# P2_AudioInput.net
KiCad netlist of a schematic drawn in Altium Designer
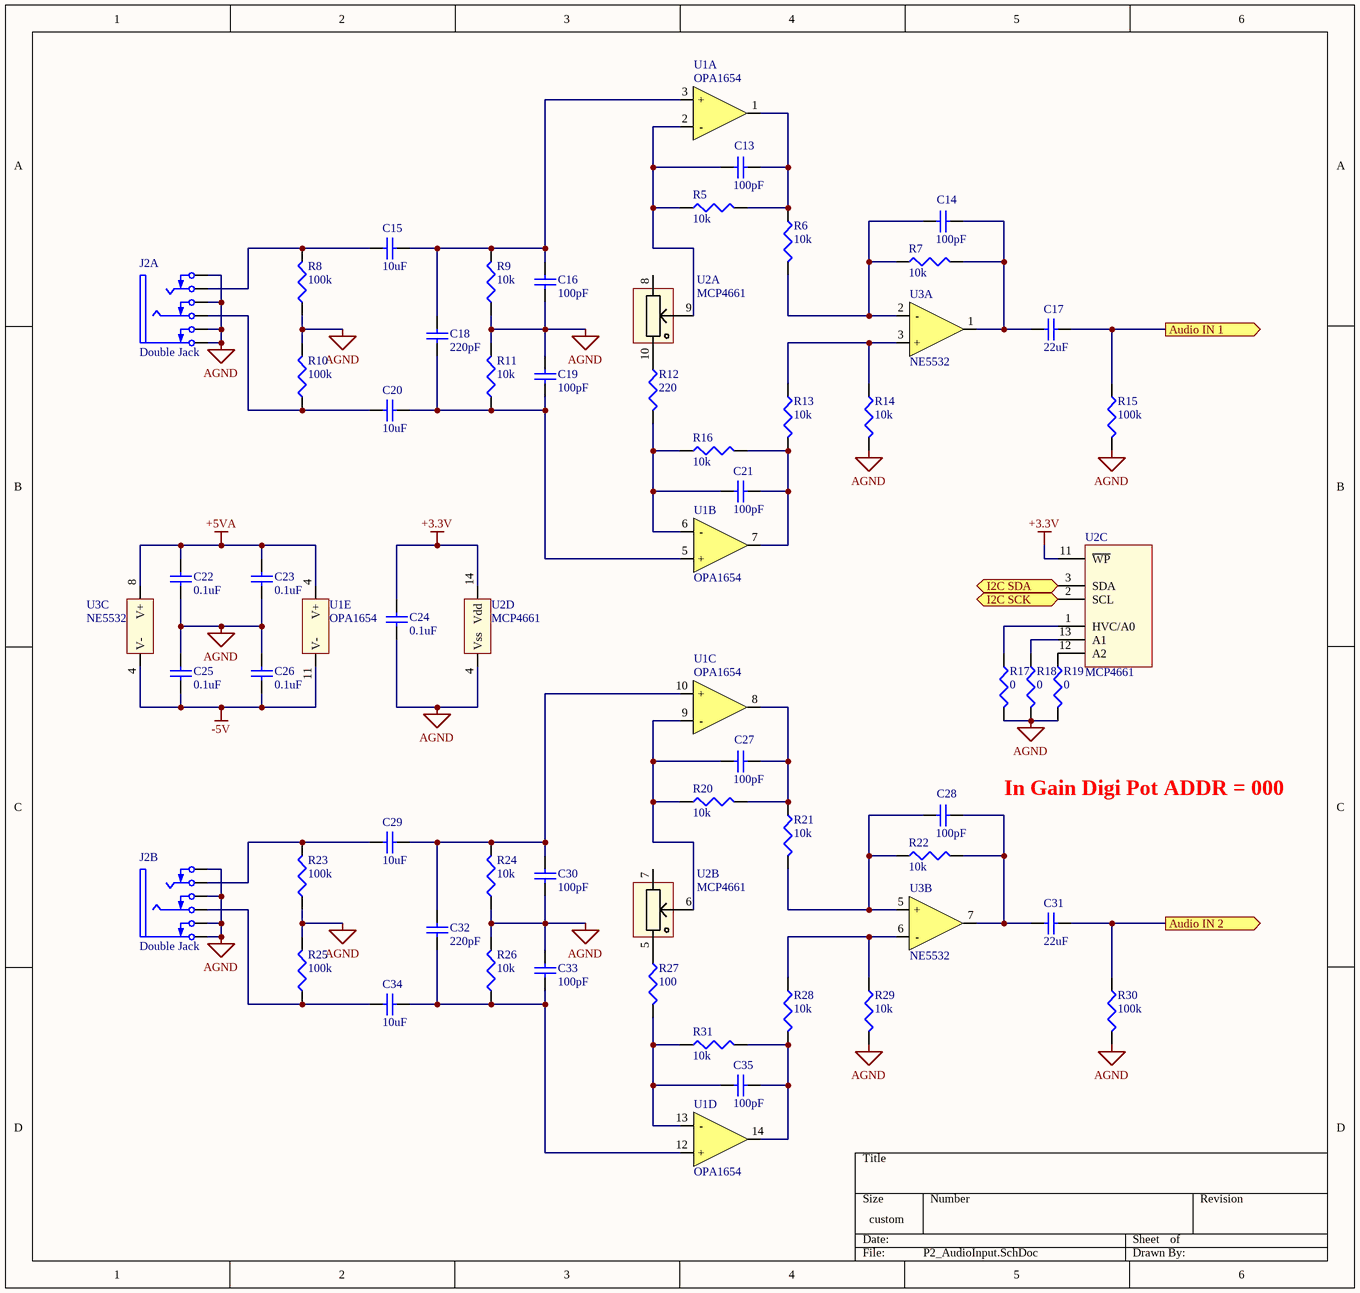
[diagram p0: P2_AudioInput.SchDoc]

(export (version "E")
  (design (tool "Eeschema 10.0.6"))
  (components
    (comp (ref "C13")
      (value "100pF")
      (footprint "CAP 0603 (1608 metric)")
      (description "Capacitor (Semiconductor SIM Model)")
      (libsource (lib "Miscellaneous Devices") (part "Cap Semi"))
    )
    (comp (ref "C14")
      (value "100pF")
      (footprint "CAP 0603 (1608 metric)")
      (description "Capacitor (Semiconductor SIM Model)")
      (libsource (lib "Miscellaneous Devices") (part "Cap Semi"))
    )
    (comp (ref "C15")
      (value "10uF")
      (footprint "CAP 0603 (1608 metric)")
      (description "Capacitor (Semiconductor SIM Model)")
      (libsource (lib "Miscellaneous Devices") (part "Cap Semi"))
    )
    (comp (ref "C16")
      (value "100pF")
      (footprint "CAP 0603 (1608 metric)")
      (description "Capacitor (Semiconductor SIM Model)")
      (libsource (lib "Miscellaneous Devices") (part "Cap Semi"))
    )
    (comp (ref "C17")
      (value "22uF")
      (footprint "CAP 0603 (1608 metric)")
      (description "Capacitor (Semiconductor SIM Model)")
      (libsource (lib "Miscellaneous Devices") (part "Cap Semi"))
    )
    (comp (ref "C18")
      (value "220pF")
      (footprint "CAP 0603 (1608 metric)")
      (description "Capacitor (Semiconductor SIM Model)")
      (libsource (lib "Miscellaneous Devices") (part "Cap Semi"))
    )
    (comp (ref "C19")
      (value "100pF")
      (footprint "CAP 0603 (1608 metric)")
      (description "Capacitor (Semiconductor SIM Model)")
      (libsource (lib "Miscellaneous Devices") (part "Cap Semi"))
    )
    (comp (ref "C20")
      (value "10uF")
      (footprint "CAP 0603 (1608 metric)")
      (description "Capacitor (Semiconductor SIM Model)")
      (libsource (lib "Miscellaneous Devices") (part "Cap Semi"))
    )
    (comp (ref "C21")
      (value "100pF")
      (footprint "CAP 0603 (1608 metric)")
      (description "Capacitor (Semiconductor SIM Model)")
      (libsource (lib "Miscellaneous Devices") (part "Cap Semi"))
    )
    (comp (ref "C22")
      (value "0.1uF")
      (footprint "CAP 0603 (1608 metric)")
      (description "Capacitor (Semiconductor SIM Model)")
      (libsource (lib "Miscellaneous Devices") (part "Cap Semi"))
    )
    (comp (ref "C23")
      (value "0.1uF")
      (footprint "CAP 0603 (1608 metric)")
      (description "Capacitor (Semiconductor SIM Model)")
      (libsource (lib "Miscellaneous Devices") (part "Cap Semi"))
    )
    (comp (ref "C24")
      (value "0.1uF")
      (footprint "CAP 0603 (1608 metric)")
      (description "Capacitor (Semiconductor SIM Model)")
      (libsource (lib "Miscellaneous Devices") (part "Cap Semi"))
    )
    (comp (ref "C25")
      (value "0.1uF")
      (footprint "CAP 0603 (1608 metric)")
      (description "Capacitor (Semiconductor SIM Model)")
      (libsource (lib "Miscellaneous Devices") (part "Cap Semi"))
    )
    (comp (ref "C26")
      (value "0.1uF")
      (footprint "CAP 0603 (1608 metric)")
      (description "Capacitor (Semiconductor SIM Model)")
      (libsource (lib "Miscellaneous Devices") (part "Cap Semi"))
    )
    (comp (ref "C27")
      (value "100pF")
      (footprint "CAP 0603 (1608 metric)")
      (description "Capacitor (Semiconductor SIM Model)")
      (libsource (lib "Miscellaneous Devices") (part "Cap Semi"))
    )
    (comp (ref "C28")
      (value "100pF")
      (footprint "CAP 0603 (1608 metric)")
      (description "Capacitor (Semiconductor SIM Model)")
      (libsource (lib "Miscellaneous Devices") (part "Cap Semi"))
    )
    (comp (ref "C29")
      (value "10uF")
      (footprint "CAP 0603 (1608 metric)")
      (description "Capacitor (Semiconductor SIM Model)")
      (libsource (lib "Miscellaneous Devices") (part "Cap Semi"))
    )
    (comp (ref "C30")
      (value "100pF")
      (footprint "CAP 0603 (1608 metric)")
      (description "Capacitor (Semiconductor SIM Model)")
      (libsource (lib "Miscellaneous Devices") (part "Cap Semi"))
    )
    (comp (ref "C31")
      (value "22uF")
      (footprint "CAP 0603 (1608 metric)")
      (description "Capacitor (Semiconductor SIM Model)")
      (libsource (lib "Miscellaneous Devices") (part "Cap Semi"))
    )
    (comp (ref "C32")
      (value "220pF")
      (footprint "CAP 0603 (1608 metric)")
      (description "Capacitor (Semiconductor SIM Model)")
      (libsource (lib "Miscellaneous Devices") (part "Cap Semi"))
    )
    (comp (ref "C33")
      (value "100pF")
      (footprint "CAP 0603 (1608 metric)")
      (description "Capacitor (Semiconductor SIM Model)")
      (libsource (lib "Miscellaneous Devices") (part "Cap Semi"))
    )
    (comp (ref "C34")
      (value "10uF")
      (footprint "CAP 0603 (1608 metric)")
      (description "Capacitor (Semiconductor SIM Model)")
      (libsource (lib "Miscellaneous Devices") (part "Cap Semi"))
    )
    (comp (ref "C35")
      (value "100pF")
      (footprint "CAP 0603 (1608 metric)")
      (description "Capacitor (Semiconductor SIM Model)")
      (libsource (lib "Miscellaneous Devices") (part "Cap Semi"))
    )
    (comp (ref "J2")
      (value "Double Jack")
      (description "Dual Jack stereo bypassed")
      (libsource (lib "FilterPoC") (part "Dual TRS Jack Bypassed"))
    )
    (comp (ref "R5")
      (value "10k")
      (footprint "RES 0603 (1608 metric)")
      (description "Resistor")
      (libsource (lib "Miscellaneous Devices") (part "Res3"))
    )
    (comp (ref "R6")
      (value "10k")
      (footprint "RES 0603 (1608 metric)")
      (description "Resistor")
      (libsource (lib "Miscellaneous Devices") (part "Res3"))
    )
    (comp (ref "R7")
      (value "10k")
      (footprint "RES 0603 (1608 metric)")
      (description "Resistor")
      (libsource (lib "Miscellaneous Devices") (part "Res3"))
    )
    (comp (ref "R8")
      (value "100k")
      (footprint "RES 0603 (1608 metric)")
      (description "Resistor")
      (libsource (lib "Miscellaneous Devices") (part "Res3"))
    )
    (comp (ref "R9")
      (value "10k")
      (footprint "RES 0603 (1608 metric)")
      (description "Resistor")
      (libsource (lib "Miscellaneous Devices") (part "Res3"))
    )
    (comp (ref "R10")
      (value "100k")
      (footprint "RES 0603 (1608 metric)")
      (description "Resistor")
      (libsource (lib "Miscellaneous Devices") (part "Res3"))
    )
    (comp (ref "R11")
      (value "10k")
      (footprint "RES 0603 (1608 metric)")
      (description "Resistor")
      (libsource (lib "Miscellaneous Devices") (part "Res3"))
    )
    (comp (ref "R12")
      (value "220")
      (footprint "RES 0603 (1608 metric)")
      (description "Resistor")
      (libsource (lib "Miscellaneous Devices") (part "Res3"))
    )
    (comp (ref "R13")
      (value "10k")
      (footprint "RES 0603 (1608 metric)")
      (description "Resistor")
      (libsource (lib "Miscellaneous Devices") (part "Res3"))
    )
    (comp (ref "R14")
      (value "10k")
      (footprint "RES 0603 (1608 metric)")
      (description "Resistor")
      (libsource (lib "Miscellaneous Devices") (part "Res3"))
    )
    (comp (ref "R15")
      (value "100k")
      (footprint "RES 0603 (1608 metric)")
      (description "Resistor")
      (libsource (lib "Miscellaneous Devices") (part "Res3"))
    )
    (comp (ref "R16")
      (value "10k")
      (footprint "RES 0603 (1608 metric)")
      (description "Resistor")
      (libsource (lib "Miscellaneous Devices") (part "Res3"))
    )
    (comp (ref "R17")
      (value "0")
      (footprint "RES 0603 (1608 metric)")
      (description "Resistor")
      (libsource (lib "Miscellaneous Devices") (part "Res3"))
    )
    (comp (ref "R18")
      (value "0")
      (footprint "RES 0603 (1608 metric)")
      (description "Resistor")
      (libsource (lib "Miscellaneous Devices") (part "Res3"))
    )
    (comp (ref "R19")
      (value "0")
      (footprint "RES 0603 (1608 metric)")
      (description "Resistor")
      (libsource (lib "Miscellaneous Devices") (part "Res3"))
    )
    (comp (ref "R20")
      (value "10k")
      (footprint "RES 0603 (1608 metric)")
      (description "Resistor")
      (libsource (lib "Miscellaneous Devices") (part "Res3"))
    )
    (comp (ref "R21")
      (value "10k")
      (footprint "RES 0603 (1608 metric)")
      (description "Resistor")
      (libsource (lib "Miscellaneous Devices") (part "Res3"))
    )
    (comp (ref "R22")
      (value "10k")
      (footprint "RES 0603 (1608 metric)")
      (description "Resistor")
      (libsource (lib "Miscellaneous Devices") (part "Res3"))
    )
    (comp (ref "R23")
      (value "100k")
      (footprint "RES 0603 (1608 metric)")
      (description "Resistor")
      (libsource (lib "Miscellaneous Devices") (part "Res3"))
    )
    (comp (ref "R24")
      (value "10k")
      (footprint "RES 0603 (1608 metric)")
      (description "Resistor")
      (libsource (lib "Miscellaneous Devices") (part "Res3"))
    )
    (comp (ref "R25")
      (value "100k")
      (footprint "RES 0603 (1608 metric)")
      (description "Resistor")
      (libsource (lib "Miscellaneous Devices") (part "Res3"))
    )
    (comp (ref "R26")
      (value "10k")
      (footprint "RES 0603 (1608 metric)")
      (description "Resistor")
      (libsource (lib "Miscellaneous Devices") (part "Res3"))
    )
    (comp (ref "R27")
      (value "100")
      (footprint "RES 0603 (1608 metric)")
      (description "Resistor")
      (libsource (lib "Miscellaneous Devices") (part "Res3"))
    )
    (comp (ref "R28")
      (value "10k")
      (footprint "RES 0603 (1608 metric)")
      (description "Resistor")
      (libsource (lib "Miscellaneous Devices") (part "Res3"))
    )
    (comp (ref "R29")
      (value "10k")
      (footprint "RES 0603 (1608 metric)")
      (description "Resistor")
      (libsource (lib "Miscellaneous Devices") (part "Res3"))
    )
    (comp (ref "R30")
      (value "100k")
      (footprint "RES 0603 (1608 metric)")
      (description "Resistor")
      (libsource (lib "Miscellaneous Devices") (part "Res3"))
    )
    (comp (ref "R31")
      (value "10k")
      (footprint "RES 0603 (1608 metric)")
      (description "Resistor")
      (libsource (lib "Miscellaneous Devices") (part "Res3"))
    )
    (comp (ref "U1")
      (value "OPA1654")
      (description "Quad Audio OpAmp")
      (libsource (lib "FilterPoC") (part "OPA1654"))
    )
    (comp (ref "U2")
      (value "MCP4661")
      (description "Dual DigiPot non volatile I2C")
      (libsource (lib "FilterPoC") (part "MCP4661"))
    )
    (comp (ref "U3")
      (value "NE5532")
      (description "Dual Audio OpAmp")
      (libsource (lib "FilterPoC") (part "NE5532"))
    )
  )
  (nets
    (net (code "1") (name "+3.3V") (class "Default")
      (node (ref "C24") (pin "1") (pinfunction "1_1") (pintype "passive"))
      (node (ref "U2") (pin "11") (pinfunction "~{WP}_11") (pintype "passive"))
      (node (ref "U2") (pin "14") (pinfunction "Vdd_14") (pintype "power_in"))
    )
    (net (code "2") (name "+5VA") (class "Default")
      (node (ref "C22") (pin "1") (pinfunction "1_1") (pintype "passive"))
      (node (ref "C23") (pin "1") (pinfunction "1_1") (pintype "passive"))
      (node (ref "U1") (pin "4") (pinfunction "V+_4") (pintype "power_in"))
      (node (ref "U3") (pin "8") (pinfunction "V+_8") (pintype "power_in"))
    )
    (net (code "3") (name "-5V") (class "Default")
      (node (ref "C25") (pin "2") (pinfunction "2_2") (pintype "passive"))
      (node (ref "C26") (pin "2") (pinfunction "2_2") (pintype "passive"))
      (node (ref "U1") (pin "11") (pinfunction "V-_11") (pintype "power_in"))
      (node (ref "U3") (pin "4") (pinfunction "V-_4") (pintype "power_in"))
    )
    (net (code "4") (name "/Audio IN 1") (class "Default")
      (node (ref "C17") (pin "1") (pinfunction "1_1") (pintype "passive"))
      (node (ref "R15") (pin "1") (pinfunction "1_1") (pintype "passive"))
    )
    (net (code "5") (name "/Audio IN 2") (class "Default")
      (node (ref "C31") (pin "1") (pinfunction "1_1") (pintype "passive"))
      (node (ref "R30") (pin "1") (pinfunction "1_1") (pintype "passive"))
    )
    (net (code "6") (name "/I2C SCK") (class "Default")
      (node (ref "U2") (pin "2") (pinfunction "SCL_2") (pintype "passive"))
    )
    (net (code "7") (name "/I2C SDA") (class "Default")
      (node (ref "U2") (pin "3") (pinfunction "SDA_3") (pintype "passive"))
    )
    (net (code "8") (name "AGND") (class "Default")
      (node (ref "C16") (pin "2") (pinfunction "2_2") (pintype "passive"))
      (node (ref "C19") (pin "1") (pinfunction "1_1") (pintype "passive"))
      (node (ref "C22") (pin "2") (pinfunction "2_2") (pintype "passive"))
      (node (ref "C23") (pin "2") (pinfunction "2_2") (pintype "passive"))
      (node (ref "C24") (pin "2") (pinfunction "2_2") (pintype "passive"))
      (node (ref "C25") (pin "1") (pinfunction "1_1") (pintype "passive"))
      (node (ref "C26") (pin "1") (pinfunction "1_1") (pintype "passive"))
      (node (ref "C30") (pin "2") (pinfunction "2_2") (pintype "passive"))
      (node (ref "C33") (pin "1") (pinfunction "1_1") (pintype "passive"))
      (node (ref "J2") (pin "1") (pinfunction "SB_1") (pintype "passive"))
      (node (ref "J2") (pin "10") (pinfunction "S_10") (pintype "power_in"))
      (node (ref "J2") (pin "2") (pinfunction "RB_2") (pintype "passive"))
      (node (ref "J2") (pin "3") (pinfunction "TB_3") (pintype "passive"))
      (node (ref "J2") (pin "4") (pinfunction "S_4") (pintype "power_in"))
      (node (ref "J2") (pin "7") (pinfunction "SB_7") (pintype "passive"))
      (node (ref "J2") (pin "8") (pinfunction "RB_8") (pintype "passive"))
      (node (ref "J2") (pin "9") (pinfunction "TB_9") (pintype "passive"))
      (node (ref "R10") (pin "2") (pinfunction "2_2") (pintype "passive"))
      (node (ref "R11") (pin "2") (pinfunction "2_2") (pintype "passive"))
      (node (ref "R14") (pin "2") (pinfunction "2_2") (pintype "passive"))
      (node (ref "R15") (pin "2") (pinfunction "2_2") (pintype "passive"))
      (node (ref "R17") (pin "2") (pinfunction "2_2") (pintype "passive"))
      (node (ref "R18") (pin "2") (pinfunction "2_2") (pintype "passive"))
      (node (ref "R19") (pin "2") (pinfunction "2_2") (pintype "passive"))
      (node (ref "R23") (pin "1") (pinfunction "1_1") (pintype "passive"))
      (node (ref "R24") (pin "1") (pinfunction "1_1") (pintype "passive"))
      (node (ref "R25") (pin "2") (pinfunction "2_2") (pintype "passive"))
      (node (ref "R26") (pin "2") (pinfunction "2_2") (pintype "passive"))
      (node (ref "R29") (pin "2") (pinfunction "2_2") (pintype "passive"))
      (node (ref "R30") (pin "2") (pinfunction "2_2") (pintype "passive"))
      (node (ref "R8") (pin "1") (pinfunction "1_1") (pintype "passive"))
      (node (ref "R9") (pin "1") (pinfunction "1_1") (pintype "passive"))
      (node (ref "U2") (pin "4") (pinfunction "Vss_4") (pintype "power_in"))
    )
    (net (code "9") (name "Net-(J2A-R)") (class "Default")
      (node (ref "C20") (pin "2") (pinfunction "2_2") (pintype "passive"))
      (node (ref "J2") (pin "11") (pinfunction "R_11") (pintype "passive"))
      (node (ref "R10") (pin "1") (pinfunction "1_1") (pintype "passive"))
    )
    (net (code "10") (name "Net-(J2A-T)") (class "Default")
      (node (ref "C15") (pin "2") (pinfunction "2_2") (pintype "passive"))
      (node (ref "J2") (pin "12") (pinfunction "T_12") (pintype "passive"))
      (node (ref "R8") (pin "2") (pinfunction "2_2") (pintype "passive"))
    )
    (net (code "11") (name "Net-(J2B-R)") (class "Default")
      (node (ref "C34") (pin "2") (pinfunction "2_2") (pintype "passive"))
      (node (ref "J2") (pin "5") (pinfunction "R_5") (pintype "passive"))
      (node (ref "R25") (pin "1") (pinfunction "1_1") (pintype "passive"))
    )
    (net (code "12") (name "Net-(J2B-T)") (class "Default")
      (node (ref "C29") (pin "2") (pinfunction "2_2") (pintype "passive"))
      (node (ref "J2") (pin "6") (pinfunction "T_6") (pintype "passive"))
      (node (ref "R23") (pin "2") (pinfunction "2_2") (pintype "passive"))
    )
    (net (code "13") (name "Net-(U1A-+)") (class "Default")
      (node (ref "C15") (pin "1") (pinfunction "1_1") (pintype "passive"))
      (node (ref "C16") (pin "1") (pinfunction "1_1") (pintype "passive"))
      (node (ref "C18") (pin "1") (pinfunction "1_1") (pintype "passive"))
      (node (ref "R9") (pin "2") (pinfunction "2_2") (pintype "passive"))
      (node (ref "U1") (pin "3") (pinfunction "+_3") (pintype "passive"))
    )
    (net (code "14") (name "Net-(U1A--)") (class "Default")
      (node (ref "C13") (pin "1") (pinfunction "1_1") (pintype "passive"))
      (node (ref "R5") (pin "1") (pinfunction "1_1") (pintype "passive"))
      (node (ref "U1") (pin "2") (pinfunction "-_2") (pintype "passive"))
      (node (ref "U2") (pin "9") (pinfunction "P0W_9") (pintype "passive"))
    )
    (net (code "15") (name "Net-(U1A-OUT)") (class "Default")
      (node (ref "C13") (pin "2") (pinfunction "2_2") (pintype "passive"))
      (node (ref "R5") (pin "2") (pinfunction "2_2") (pintype "passive"))
      (node (ref "R6") (pin "1") (pinfunction "1_1") (pintype "passive"))
      (node (ref "U1") (pin "1") (pinfunction "OUT_1") (pintype "passive"))
    )
    (net (code "16") (name "Net-(U1B-+)") (class "Default")
      (node (ref "C18") (pin "2") (pinfunction "2_2") (pintype "passive"))
      (node (ref "C19") (pin "2") (pinfunction "2_2") (pintype "passive"))
      (node (ref "C20") (pin "1") (pinfunction "1_1") (pintype "passive"))
      (node (ref "R11") (pin "1") (pinfunction "1_1") (pintype "passive"))
      (node (ref "U1") (pin "5") (pinfunction "+_5") (pintype "passive"))
    )
    (net (code "17") (name "Net-(U1B--)") (class "Default")
      (node (ref "C21") (pin "1") (pinfunction "1_1") (pintype "passive"))
      (node (ref "R12") (pin "2") (pinfunction "2_2") (pintype "passive"))
      (node (ref "R16") (pin "1") (pinfunction "1_1") (pintype "passive"))
      (node (ref "U1") (pin "6") (pinfunction "-_6") (pintype "passive"))
    )
    (net (code "18") (name "Net-(U1B-OUT)") (class "Default")
      (node (ref "C21") (pin "2") (pinfunction "2_2") (pintype "passive"))
      (node (ref "R13") (pin "2") (pinfunction "2_2") (pintype "passive"))
      (node (ref "R16") (pin "2") (pinfunction "2_2") (pintype "passive"))
      (node (ref "U1") (pin "7") (pinfunction "OUT_7") (pintype "passive"))
    )
    (net (code "19") (name "Net-(U1C-+)") (class "Default")
      (node (ref "C29") (pin "1") (pinfunction "1_1") (pintype "passive"))
      (node (ref "C30") (pin "1") (pinfunction "1_1") (pintype "passive"))
      (node (ref "C32") (pin "1") (pinfunction "1_1") (pintype "passive"))
      (node (ref "R24") (pin "2") (pinfunction "2_2") (pintype "passive"))
      (node (ref "U1") (pin "10") (pinfunction "+_10") (pintype "passive"))
    )
    (net (code "20") (name "Net-(U1C--)") (class "Default")
      (node (ref "C27") (pin "1") (pinfunction "1_1") (pintype "passive"))
      (node (ref "R20") (pin "1") (pinfunction "1_1") (pintype "passive"))
      (node (ref "U1") (pin "9") (pinfunction "-_9") (pintype "passive"))
      (node (ref "U2") (pin "6") (pinfunction "P1W_6") (pintype "passive"))
    )
    (net (code "21") (name "Net-(U1C-OUT)") (class "Default")
      (node (ref "C27") (pin "2") (pinfunction "2_2") (pintype "passive"))
      (node (ref "R20") (pin "2") (pinfunction "2_2") (pintype "passive"))
      (node (ref "R21") (pin "1") (pinfunction "1_1") (pintype "passive"))
      (node (ref "U1") (pin "8") (pinfunction "OUT_8") (pintype "passive"))
    )
    (net (code "22") (name "Net-(U1D-+)") (class "Default")
      (node (ref "C32") (pin "2") (pinfunction "2_2") (pintype "passive"))
      (node (ref "C33") (pin "2") (pinfunction "2_2") (pintype "passive"))
      (node (ref "C34") (pin "1") (pinfunction "1_1") (pintype "passive"))
      (node (ref "R26") (pin "1") (pinfunction "1_1") (pintype "passive"))
      (node (ref "U1") (pin "12") (pinfunction "+_12") (pintype "passive"))
    )
    (net (code "23") (name "Net-(U1D--)") (class "Default")
      (node (ref "C35") (pin "1") (pinfunction "1_1") (pintype "passive"))
      (node (ref "R27") (pin "2") (pinfunction "2_2") (pintype "passive"))
      (node (ref "R31") (pin "1") (pinfunction "1_1") (pintype "passive"))
      (node (ref "U1") (pin "13") (pinfunction "-_13") (pintype "passive"))
    )
    (net (code "24") (name "Net-(U1D-OUT)") (class "Default")
      (node (ref "C35") (pin "2") (pinfunction "2_2") (pintype "passive"))
      (node (ref "R28") (pin "2") (pinfunction "2_2") (pintype "passive"))
      (node (ref "R31") (pin "2") (pinfunction "2_2") (pintype "passive"))
      (node (ref "U1") (pin "14") (pinfunction "OUT_14") (pintype "passive"))
    )
    (net (code "25") (name "Net-(U2A-P0B)") (class "Default")
      (node (ref "R12") (pin "1") (pinfunction "1_1") (pintype "passive"))
      (node (ref "U2") (pin "10") (pinfunction "P0B_10") (pintype "passive"))
    )
    (net (code "26") (name "Net-(U2B-P1B)") (class "Default")
      (node (ref "R27") (pin "1") (pinfunction "1_1") (pintype "passive"))
      (node (ref "U2") (pin "5") (pinfunction "P1B_5") (pintype "passive"))
    )
    (net (code "27") (name "Net-(U2C-A1)") (class "Default")
      (node (ref "R18") (pin "1") (pinfunction "1_1") (pintype "passive"))
      (node (ref "U2") (pin "13") (pinfunction "A1_13") (pintype "power_in"))
    )
    (net (code "28") (name "Net-(U2C-A2)") (class "Default")
      (node (ref "R19") (pin "1") (pinfunction "1_1") (pintype "passive"))
      (node (ref "U2") (pin "12") (pinfunction "A2_12") (pintype "power_in"))
    )
    (net (code "29") (name "Net-(U2C-HVC{slash}A0)") (class "Default")
      (node (ref "R17") (pin "1") (pinfunction "1_1") (pintype "passive"))
      (node (ref "U2") (pin "1") (pinfunction "HVC/A0_1") (pintype "power_in"))
    )
    (net (code "30") (name "Net-(U3A-+)") (class "Default")
      (node (ref "R13") (pin "1") (pinfunction "1_1") (pintype "passive"))
      (node (ref "R14") (pin "1") (pinfunction "1_1") (pintype "passive"))
      (node (ref "U3") (pin "3") (pinfunction "+_3") (pintype "passive"))
    )
    (net (code "31") (name "Net-(U3A--)") (class "Default")
      (node (ref "C14") (pin "1") (pinfunction "1_1") (pintype "passive"))
      (node (ref "R6") (pin "2") (pinfunction "2_2") (pintype "passive"))
      (node (ref "R7") (pin "1") (pinfunction "1_1") (pintype "passive"))
      (node (ref "U3") (pin "2") (pinfunction "-_2") (pintype "passive"))
    )
    (net (code "32") (name "Net-(U3A-OUT)") (class "Default")
      (node (ref "C14") (pin "2") (pinfunction "2_2") (pintype "passive"))
      (node (ref "C17") (pin "2") (pinfunction "2_2") (pintype "passive"))
      (node (ref "R7") (pin "2") (pinfunction "2_2") (pintype "passive"))
      (node (ref "U3") (pin "1") (pinfunction "OUT_1") (pintype "passive"))
    )
    (net (code "33") (name "Net-(U3B-+)") (class "Default")
      (node (ref "C28") (pin "1") (pinfunction "1_1") (pintype "passive"))
      (node (ref "R21") (pin "2") (pinfunction "2_2") (pintype "passive"))
      (node (ref "R22") (pin "1") (pinfunction "1_1") (pintype "passive"))
      (node (ref "U3") (pin "5") (pinfunction "+_5") (pintype "passive"))
    )
    (net (code "34") (name "Net-(U3B--)") (class "Default")
      (node (ref "R28") (pin "1") (pinfunction "1_1") (pintype "passive"))
      (node (ref "R29") (pin "1") (pinfunction "1_1") (pintype "passive"))
      (node (ref "U3") (pin "6") (pinfunction "-_6") (pintype "passive"))
    )
    (net (code "35") (name "Net-(U3B-OUT)") (class "Default")
      (node (ref "C28") (pin "2") (pinfunction "2_2") (pintype "passive"))
      (node (ref "C31") (pin "2") (pinfunction "2_2") (pintype "passive"))
      (node (ref "R22") (pin "2") (pinfunction "2_2") (pintype "passive"))
      (node (ref "U3") (pin "7") (pinfunction "OUT_7") (pintype "passive"))
    )
    (net (code "36") (name "unconnected-(U2A-P0A-Pad8)") (class "Default")
      (node (ref "U2") (pin "8") (pinfunction "P0A_8") (pintype "passive"))
    )
    (net (code "37") (name "unconnected-(U2B-P1A-Pad7)") (class "Default")
      (node (ref "U2") (pin "7") (pinfunction "P1A_7") (pintype "passive"))
    )
  )
)
